# IOExpander.net
KiCad netlist of a schematic drawn in Altium Designer
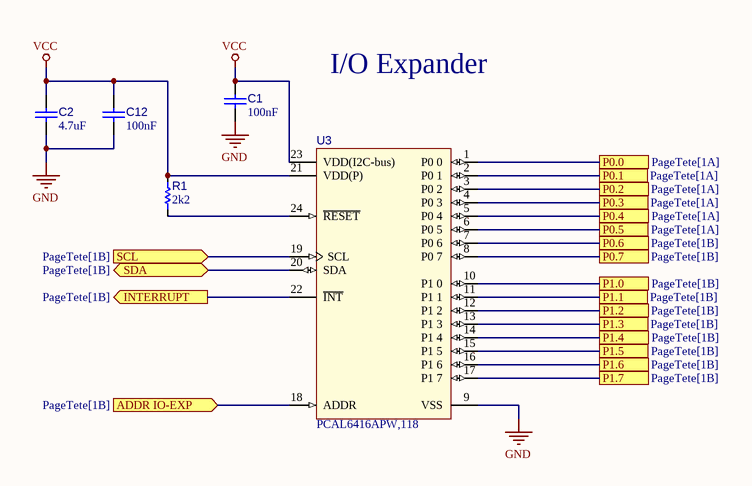
[diagram p0: IOExpander.SchDoc]

(export (version "E")
  (design (tool "Eeschema 10.0.6"))
  (components
    (comp (ref "C1")
      (value "100nF")
      (footprint "C_1005[0402]")
      (description "Capacitor type 1")
      (fields (field (name "TOLERANCE") "10%") (field (name "Comment") "Cap 100nF 0402"))
      (libsource (lib "TEP_243-Altium_RLC-Lib") (part "CAP001"))
    )
    (comp (ref "C2")
      (value "4.7uF")
      (footprint "C_2012[0805]")
      (description "Capacitor type 1")
      (fields (field (name "TOLERANCE") "10%") (field (name "Comment") "Cap 4.7uF 0805"))
      (libsource (lib "TEP_243-Altium_RLC-Lib") (part "CAP003"))
    )
    (comp (ref "C12")
      (value "100nF")
      (footprint "C_1005[0402]")
      (description "Capacitor type 1")
      (fields (field (name "TOLERANCE") "10%") (field (name "Comment") "Cap 100nF 0402"))
      (libsource (lib "TEP_243-Altium_RLC-Lib") (part "CAP001"))
    )
    (comp (ref "R1")
      (value "2k2")
      (footprint "R_1005[0402]")
      (description "Resistor type 1")
      (fields (field (name "TOLERANCE") "1%") (field (name "Comment") "Res 2k2 1% 0402"))
      (libsource (lib "TEP_243-Altium_RLC-Lib") (part "RES008"))
    )
    (comp (ref "U3")
      (value "PCAL6416APW,118")
      (footprint "U_TSSOP24_SOT355-1-IPC_B")
      (description "IC I/O EXPANDER 16BIT 24TSSOP")
      (libsource (lib "243-336_MP_Manette_ETU") (part "U_PCAL6416APW"))
    )
  )
  (nets
    (net (code "1") (name "/ADDR IO-EXP") (class "Default")
      (node (ref "U3") (pin "18") (pinfunction "ADDR_18") (pintype "input"))
    )
    (net (code "2") (name "/INTERRUPT") (class "Default")
      (node (ref "U3") (pin "22") (pinfunction "~{INT}_22") (pintype "open_collector"))
    )
    (net (code "3") (name "/P0.0") (class "Default")
      (node (ref "U3") (pin "1") (pinfunction "P0_0_1") (pintype "bidirectional"))
    )
    (net (code "4") (name "/P0.1") (class "Default")
      (node (ref "U3") (pin "2") (pinfunction "P0_1_2") (pintype "bidirectional"))
    )
    (net (code "5") (name "/P0.2") (class "Default")
      (node (ref "U3") (pin "3") (pinfunction "P0_2_3") (pintype "bidirectional"))
    )
    (net (code "6") (name "/P0.3") (class "Default")
      (node (ref "U3") (pin "4") (pinfunction "P0_3_4") (pintype "bidirectional"))
    )
    (net (code "7") (name "/P0.4") (class "Default")
      (node (ref "U3") (pin "5") (pinfunction "P0_4_5") (pintype "bidirectional"))
    )
    (net (code "8") (name "/P0.5") (class "Default")
      (node (ref "U3") (pin "6") (pinfunction "P0_5_6") (pintype "bidirectional"))
    )
    (net (code "9") (name "/P0.6") (class "Default")
      (node (ref "U3") (pin "7") (pinfunction "P0_6_7") (pintype "bidirectional"))
    )
    (net (code "10") (name "/P0.7") (class "Default")
      (node (ref "U3") (pin "8") (pinfunction "P0_7_8") (pintype "bidirectional"))
    )
    (net (code "11") (name "/P1.0") (class "Default")
      (node (ref "U3") (pin "10") (pinfunction "P1_0_10") (pintype "bidirectional"))
    )
    (net (code "12") (name "/P1.1") (class "Default")
      (node (ref "U3") (pin "11") (pinfunction "P1_1_11") (pintype "bidirectional"))
    )
    (net (code "13") (name "/P1.2") (class "Default")
      (node (ref "U3") (pin "12") (pinfunction "P1_2_12") (pintype "bidirectional"))
    )
    (net (code "14") (name "/P1.3") (class "Default")
      (node (ref "U3") (pin "13") (pinfunction "P1_3_13") (pintype "bidirectional"))
    )
    (net (code "15") (name "/P1.4") (class "Default")
      (node (ref "U3") (pin "14") (pinfunction "P1_4_14") (pintype "bidirectional"))
    )
    (net (code "16") (name "/P1.5") (class "Default")
      (node (ref "U3") (pin "15") (pinfunction "P1_5_15") (pintype "bidirectional"))
    )
    (net (code "17") (name "/P1.6") (class "Default")
      (node (ref "U3") (pin "16") (pinfunction "P1_6_16") (pintype "bidirectional"))
    )
    (net (code "18") (name "/P1.7") (class "Default")
      (node (ref "U3") (pin "17") (pinfunction "P1_7_17") (pintype "bidirectional"))
    )
    (net (code "19") (name "/SCL") (class "Default")
      (node (ref "U3") (pin "19") (pinfunction "SCL_19") (pintype "input"))
    )
    (net (code "20") (name "/SDA") (class "Default")
      (node (ref "U3") (pin "20") (pinfunction "SDA_20") (pintype "bidirectional"))
    )
    (net (code "21") (name "GND") (class "Default")
      (node (ref "C1") (pin "1") (pinfunction "1_1") (pintype "passive"))
      (node (ref "C12") (pin "1") (pinfunction "1_1") (pintype "passive"))
      (node (ref "C2") (pin "1") (pinfunction "1_1") (pintype "passive"))
      (node (ref "U3") (pin "9") (pinfunction "VSS_9") (pintype "power_in"))
    )
    (net (code "22") (name "Net-(U3-~{RESET})") (class "Default")
      (node (ref "R1") (pin "1") (pinfunction "1_1") (pintype "passive"))
      (node (ref "U3") (pin "24") (pinfunction "~{RESET}_24") (pintype "input"))
    )
    (net (code "23") (name "VCC") (class "Default")
      (node (ref "C1") (pin "2") (pinfunction "2_2") (pintype "passive"))
      (node (ref "C12") (pin "2") (pinfunction "2_2") (pintype "passive"))
      (node (ref "C2") (pin "2") (pinfunction "2_2") (pintype "passive"))
      (node (ref "R1") (pin "2") (pinfunction "2_2") (pintype "passive"))
      (node (ref "U3") (pin "21") (pinfunction "VDD(P)_21") (pintype "power_in"))
      (node (ref "U3") (pin "23") (pinfunction "VDD(I2C-bus)_23") (pintype "power_in"))
    )
  )
)
